# Schematic_Sensing_Module.net
KiCad netlist of a schematic drawn in EAGLE
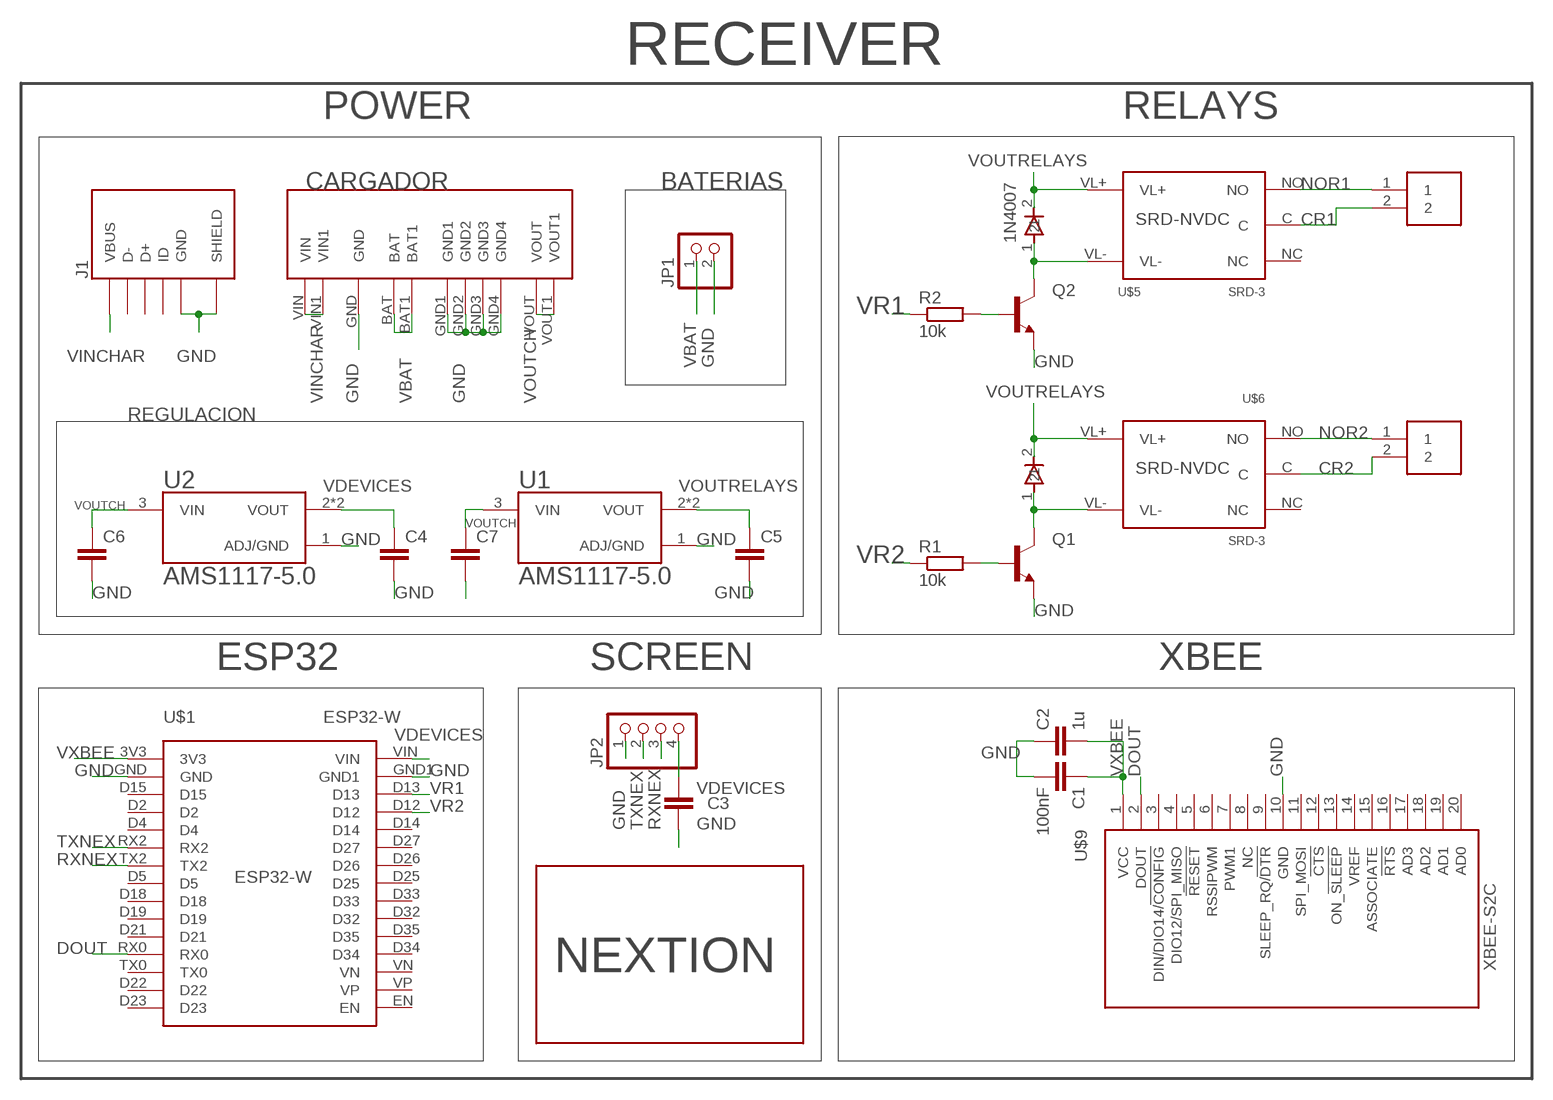
[diagram p0: schematic, sheet 1]

(export (version "E")
  (design (tool "Eeschema 10.0.6"))
  (components
    (comp (ref "1N4007")
      (value "1N4007SMA")
      (footprint "eagle-import:SMA")
      (libsource (lib "eagle-import") (part "1N4007SMA"))
    )
    (comp (ref "1N4007SMA")
      (value "1N4007SMA")
      (footprint "eagle-import:SMA")
      (libsource (lib "eagle-import") (part "1N4007SMA"))
    )
    (comp (ref "C1")
      (value "100nF")
      (footprint "eagle-import:C1206")
      (libsource (lib "eagle-import") (part "C-EUC1206"))
    )
    (comp (ref "C2")
      (value "1u")
      (footprint "eagle-import:C1206")
      (libsource (lib "eagle-import") (part "C-EUC1206"))
    )
    (comp (ref "C3")
      (value "100nF")
      (footprint "eagle-import:C1206")
      (libsource (lib "eagle-import") (part "C-EUC1206"))
    )
    (comp (ref "C4")
      (value "C-EUC1206")
      (footprint "eagle-import:C1206")
      (libsource (lib "eagle-import") (part "C-EUC1206"))
    )
    (comp (ref "C5")
      (value "C-EUC1206")
      (footprint "eagle-import:C1206")
      (libsource (lib "eagle-import") (part "C-EUC1206"))
    )
    (comp (ref "C6")
      (value "C-EUC1206")
      (footprint "eagle-import:C1206")
      (libsource (lib "eagle-import") (part "C-EUC1206"))
    )
    (comp (ref "C7")
      (value "C-EUC1206")
      (footprint "eagle-import:C1206")
      (libsource (lib "eagle-import") (part "C-EUC1206"))
    )
    (comp (ref "CARGADOR")
      (value "MODULO_CARGA_5V")
      (footprint "eagle-import:MODULO_CARGA_5V")
      (libsource (lib "eagle-import") (part "MODULO_CARGA_5V"))
    )
    (comp (ref "J1")
      (value "USB3090-XX-X_REVE")
      (footprint "eagle-import:GCT_USB3090-XX-X_REVE")
      (fields (field (name "MF") "Global Connector Technology") (field (name "MP") "USB3090-30-A"))
      (libsource (lib "eagle-import") (part "USB3090-XX-X_REVE"))
    )
    (comp (ref "JP1")
      (value "PINHD-1X2")
      (footprint "eagle-import:1X02")
      (libsource (lib "eagle-import") (part "PINHD-1X2"))
    )
    (comp (ref "JP2")
      (value "PINHD-1X4")
      (footprint "eagle-import:1X04")
      (libsource (lib "eagle-import") (part "PINHD-1X4"))
    )
    (comp (ref "Q1")
      (value "MMBT2222A")
      (footprint "eagle-import:SOT23")
      (fields (field (name "MF") "ON Semiconductor"))
      (libsource (lib "eagle-import") (part "MMBT2222A"))
    )
    (comp (ref "Q2")
      (value "MMBT2222A")
      (footprint "eagle-import:SOT23")
      (fields (field (name "MF") "ON Semiconductor"))
      (libsource (lib "eagle-import") (part "MMBT2222A"))
    )
    (comp (ref "R1")
      (value "10k")
      (footprint "eagle-import:R1206")
      (libsource (lib "eagle-import") (part "R-EU_R1206"))
    )
    (comp (ref "R2")
      (value "10k")
      (footprint "eagle-import:R1206")
      (libsource (lib "eagle-import") (part "R-EU_R1206"))
    )
    (comp (ref "REL1")
      (value "TERMINAL-TB2")
      (footprint "eagle-import:TERMINAL-TB2")
      (libsource (lib "eagle-import") (part "TERMINAL-TB2"))
    )
    (comp (ref "REL2")
      (value "TERMINAL-TB2")
      (footprint "eagle-import:TERMINAL-TB2")
      (libsource (lib "eagle-import") (part "TERMINAL-TB2"))
    )
    (comp (ref "U$1")
      (value "ESP32-W")
      (footprint "eagle-import:DIP")
      (libsource (lib "eagle-import") (part "ESP32-W"))
    )
    (comp (ref "U$2")
      (value "NX4024T032")
      (footprint "eagle-import:NX4024T032")
      (libsource (lib "eagle-import") (part "NX4024T032"))
    )
    (comp (ref "U$5")
      (value "SRD-3")
      (footprint "eagle-import:SRD-N")
      (libsource (lib "eagle-import") (part "SRD-3"))
    )
    (comp (ref "U$6")
      (value "SRD-3")
      (footprint "eagle-import:SRD-N")
      (libsource (lib "eagle-import") (part "SRD-3"))
    )
    (comp (ref "U$9")
      (value "XBEE-S2C")
      (footprint "eagle-import:XBEE-DIP")
      (libsource (lib "eagle-import") (part "XBEE-S2C"))
    )
    (comp (ref "U1")
      (value "AMS1117-5.0")
      (footprint "eagle-import:SOT229P700X180-4N")
      (fields (field (name "MF") "Advanced Monolithic Systems"))
      (libsource (lib "eagle-import") (part "AMS1117-5.0"))
    )
    (comp (ref "U2")
      (value "AMS1117-5.0")
      (footprint "eagle-import:SOT229P700X180-4N")
      (fields (field (name "MF") "Advanced Monolithic Systems"))
      (libsource (lib "eagle-import") (part "AMS1117-5.0"))
    )
  )
  (nets
    (net (code "1") (name "/CR1") (class "Default")
      (node (ref "REL1") (pin "2") (pinfunction "2_2") (pintype "bidirectional"))
      (node (ref "U$5") (pin "C") (pinfunction "C_C") (pintype "bidirectional"))
    )
    (net (code "2") (name "/CR2") (class "Default")
      (node (ref "REL2") (pin "2") (pinfunction "2_2") (pintype "bidirectional"))
      (node (ref "U$6") (pin "C") (pinfunction "C_C") (pintype "bidirectional"))
    )
    (net (code "3") (name "/DOUT") (class "Default")
      (node (ref "U$1") (pin "RX0") (pinfunction "RX0_RX0") (pintype "bidirectional"))
      (node (ref "U$9") (pin "2") (pinfunction "DOUT_2") (pintype "bidirectional"))
    )
    (net (code "4") (name "/GND") (class "Default")
      (node (ref "C1") (pin "2") (pinfunction "2_2") (pintype "passive"))
      (node (ref "C2") (pin "1") (pinfunction "1_1") (pintype "passive"))
      (node (ref "C3") (pin "2") (pinfunction "2_2") (pintype "passive"))
      (node (ref "C4") (pin "2") (pinfunction "2_2") (pintype "passive"))
      (node (ref "C5") (pin "2") (pinfunction "2_2") (pintype "passive"))
      (node (ref "C6") (pin "2") (pinfunction "2_2") (pintype "passive"))
      (node (ref "C7") (pin "2") (pinfunction "2_2") (pintype "passive"))
      (node (ref "CARGADOR") (pin "GND") (pinfunction "GND_GND") (pintype "bidirectional"))
      (node (ref "CARGADOR") (pin "GND1") (pinfunction "GND1_GND1") (pintype "bidirectional"))
      (node (ref "CARGADOR") (pin "GND2") (pinfunction "GND2_GND2") (pintype "bidirectional"))
      (node (ref "CARGADOR") (pin "GND3") (pinfunction "GND3_GND3") (pintype "bidirectional"))
      (node (ref "CARGADOR") (pin "GND4") (pinfunction "GND4_GND4") (pintype "bidirectional"))
      (node (ref "J1") (pin "5") (pinfunction "GND_5") (pintype "power_in"))
      (node (ref "J1") (pin "6") (pinfunction "SHIELD_6") (pintype "power_in"))
      (node (ref "J1") (pin "7") (pinfunction "SHIELD_7") (pintype "power_in"))
      (node (ref "J1") (pin "8") (pinfunction "SHIELD_8") (pintype "power_in"))
      (node (ref "J1") (pin "9") (pinfunction "SHIELD_9") (pintype "power_in"))
      (node (ref "JP1") (pin "2") (pinfunction "2_2") (pintype "passive"))
      (node (ref "JP2") (pin "1") (pinfunction "1_1") (pintype "passive"))
      (node (ref "Q1") (pin "2") (pinfunction "E_2") (pintype "passive"))
      (node (ref "Q2") (pin "2") (pinfunction "E_2") (pintype "passive"))
      (node (ref "U$1") (pin "GND") (pinfunction "GND_GND") (pintype "bidirectional"))
      (node (ref "U$1") (pin "GND1") (pinfunction "GND1_GND1") (pintype "bidirectional"))
      (node (ref "U$9") (pin "10") (pinfunction "GND_10") (pintype "bidirectional"))
      (node (ref "U1") (pin "1") (pinfunction "ADJ/GND_1") (pintype "power_in"))
      (node (ref "U2") (pin "1") (pinfunction "ADJ/GND_1") (pintype "power_in"))
    )
    (net (code "5") (name "/NOR1") (class "Default")
      (node (ref "REL1") (pin "1") (pinfunction "1_1") (pintype "bidirectional"))
      (node (ref "U$5") (pin "NO") (pinfunction "NO_NO") (pintype "bidirectional"))
    )
    (net (code "6") (name "/NOR2") (class "Default")
      (node (ref "REL2") (pin "1") (pinfunction "1_1") (pintype "bidirectional"))
      (node (ref "U$6") (pin "NO") (pinfunction "NO_NO") (pintype "bidirectional"))
    )
    (net (code "7") (name "/RXNEX") (class "Default")
      (node (ref "JP2") (pin "3") (pinfunction "3_3") (pintype "passive"))
      (node (ref "U$1") (pin "TX2") (pinfunction "TX2_TX2") (pintype "bidirectional"))
    )
    (net (code "8") (name "/TXNEX") (class "Default")
      (node (ref "JP2") (pin "2") (pinfunction "2_2") (pintype "passive"))
      (node (ref "U$1") (pin "RX2") (pinfunction "RX2_RX2") (pintype "bidirectional"))
    )
    (net (code "9") (name "/VBAT") (class "Default")
      (node (ref "CARGADOR") (pin "BAT") (pinfunction "BAT_BAT") (pintype "bidirectional"))
      (node (ref "CARGADOR") (pin "BAT1") (pinfunction "BAT1_BAT1") (pintype "bidirectional"))
      (node (ref "JP1") (pin "1") (pinfunction "1_1") (pintype "passive"))
    )
    (net (code "10") (name "/VDEVICES") (class "Default")
      (node (ref "C3") (pin "1") (pinfunction "1_1") (pintype "passive"))
      (node (ref "C4") (pin "1") (pinfunction "1_1") (pintype "passive"))
      (node (ref "JP2") (pin "4") (pinfunction "4_4") (pintype "passive"))
      (node (ref "U$1") (pin "VIN") (pinfunction "VIN_VIN") (pintype "bidirectional"))
      (node (ref "U2") (pin "2") (pinfunction "VOUT_2") (pintype "output"))
      (node (ref "U2") (pin "4") (pinfunction "VOUT_4") (pintype "output"))
    )
    (net (code "11") (name "/VINCHAR") (class "Default")
      (node (ref "CARGADOR") (pin "VIN") (pinfunction "VIN_VIN") (pintype "bidirectional"))
      (node (ref "CARGADOR") (pin "VIN1") (pinfunction "VIN1_VIN1") (pintype "bidirectional"))
      (node (ref "J1") (pin "1") (pinfunction "VBUS_1") (pintype "power_in"))
    )
    (net (code "12") (name "/VOUTCH") (class "Default")
      (node (ref "C6") (pin "1") (pinfunction "1_1") (pintype "passive"))
      (node (ref "C7") (pin "1") (pinfunction "1_1") (pintype "passive"))
      (node (ref "CARGADOR") (pin "VOUT") (pinfunction "VOUT_VOUT") (pintype "bidirectional"))
      (node (ref "CARGADOR") (pin "VOUT1") (pinfunction "VOUT1_VOUT1") (pintype "bidirectional"))
      (node (ref "U1") (pin "3") (pinfunction "VIN_3") (pintype "input"))
      (node (ref "U2") (pin "3") (pinfunction "VIN_3") (pintype "input"))
    )
    (net (code "13") (name "/VOUTRELAYS") (class "Default")
      (node (ref "1N4007") (pin "2") (pinfunction "2_2") (pintype "bidirectional"))
      (node (ref "1N4007SMA") (pin "2") (pinfunction "2_2") (pintype "bidirectional"))
      (node (ref "C5") (pin "1") (pinfunction "1_1") (pintype "passive"))
      (node (ref "U$5") (pin "VL+") (pinfunction "VL+_VL+") (pintype "bidirectional"))
      (node (ref "U$6") (pin "VL+") (pinfunction "VL+_VL+") (pintype "bidirectional"))
      (node (ref "U1") (pin "2") (pinfunction "VOUT_2") (pintype "output"))
      (node (ref "U1") (pin "4") (pinfunction "VOUT_4") (pintype "output"))
    )
    (net (code "14") (name "/VR1") (class "Default")
      (node (ref "R2") (pin "1") (pinfunction "1_1") (pintype "passive"))
      (node (ref "U$1") (pin "D13") (pinfunction "D13_D13") (pintype "bidirectional"))
    )
    (net (code "15") (name "/VR2") (class "Default")
      (node (ref "R1") (pin "1") (pinfunction "1_1") (pintype "passive"))
      (node (ref "U$1") (pin "D12") (pinfunction "D12_D12") (pintype "bidirectional"))
    )
    (net (code "16") (name "/VXBEE") (class "Default")
      (node (ref "C1") (pin "1") (pinfunction "1_1") (pintype "passive"))
      (node (ref "C2") (pin "2") (pinfunction "2_2") (pintype "passive"))
      (node (ref "U$1") (pin "3V3") (pinfunction "3V3_3V3") (pintype "bidirectional"))
      (node (ref "U$9") (pin "1") (pinfunction "VCC_1") (pintype "bidirectional"))
    )
    (net (code "17") (name "Net-(Q1-B)") (class "Default")
      (node (ref "Q1") (pin "1") (pinfunction "B_1") (pintype "passive"))
      (node (ref "R1") (pin "2") (pinfunction "2_2") (pintype "passive"))
    )
    (net (code "18") (name "Net-(Q1-C)") (class "Default")
      (node (ref "1N4007SMA") (pin "1") (pinfunction "1_1") (pintype "bidirectional"))
      (node (ref "Q1") (pin "3") (pinfunction "C_3") (pintype "passive"))
      (node (ref "U$6") (pin "VL-") (pinfunction "VL-_VL-") (pintype "bidirectional"))
    )
    (net (code "19") (name "Net-(Q2-B)") (class "Default")
      (node (ref "Q2") (pin "1") (pinfunction "B_1") (pintype "passive"))
      (node (ref "R2") (pin "2") (pinfunction "2_2") (pintype "passive"))
    )
    (net (code "20") (name "Net-(Q2-C)") (class "Default")
      (node (ref "1N4007") (pin "1") (pinfunction "1_1") (pintype "bidirectional"))
      (node (ref "Q2") (pin "3") (pinfunction "C_3") (pintype "passive"))
      (node (ref "U$5") (pin "VL-") (pinfunction "VL-_VL-") (pintype "bidirectional"))
    )
    (net (code "21") (name "unconnected-(J1-D+-Pad3)") (class "Default")
      (node (ref "J1") (pin "3") (pinfunction "D+_3") (pintype "bidirectional"))
    )
    (net (code "22") (name "unconnected-(J1-D--Pad2)") (class "Default")
      (node (ref "J1") (pin "2") (pinfunction "D-_2") (pintype "bidirectional"))
    )
    (net (code "23") (name "unconnected-(J1-ID-Pad4)") (class "Default")
      (node (ref "J1") (pin "4") (pinfunction "ID_4") (pintype "bidirectional"))
    )
    (net (code "24") (name "unconnected-(U$1-PadD2)") (class "Default")
      (node (ref "U$1") (pin "D2") (pinfunction "D2_D2") (pintype "bidirectional"))
    )
    (net (code "25") (name "unconnected-(U$1-PadD4)") (class "Default")
      (node (ref "U$1") (pin "D4") (pinfunction "D4_D4") (pintype "bidirectional"))
    )
    (net (code "26") (name "unconnected-(U$1-PadD5)") (class "Default")
      (node (ref "U$1") (pin "D5") (pinfunction "D5_D5") (pintype "bidirectional"))
    )
    (net (code "27") (name "unconnected-(U$1-PadD14)") (class "Default")
      (node (ref "U$1") (pin "D14") (pinfunction "D14_D14") (pintype "bidirectional"))
    )
    (net (code "28") (name "unconnected-(U$1-PadD15)") (class "Default")
      (node (ref "U$1") (pin "D15") (pinfunction "D15_D15") (pintype "bidirectional"))
    )
    (net (code "29") (name "unconnected-(U$1-PadD18)") (class "Default")
      (node (ref "U$1") (pin "D18") (pinfunction "D18_D18") (pintype "bidirectional"))
    )
    (net (code "30") (name "unconnected-(U$1-PadD19)") (class "Default")
      (node (ref "U$1") (pin "D19") (pinfunction "D19_D19") (pintype "bidirectional"))
    )
    (net (code "31") (name "unconnected-(U$1-PadD21)") (class "Default")
      (node (ref "U$1") (pin "D21") (pinfunction "D21_D21") (pintype "bidirectional"))
    )
    (net (code "32") (name "unconnected-(U$1-PadD22)") (class "Default")
      (node (ref "U$1") (pin "D22") (pinfunction "D22_D22") (pintype "bidirectional"))
    )
    (net (code "33") (name "unconnected-(U$1-PadD23)") (class "Default")
      (node (ref "U$1") (pin "D23") (pinfunction "D23_D23") (pintype "bidirectional"))
    )
    (net (code "34") (name "unconnected-(U$1-PadD25)") (class "Default")
      (node (ref "U$1") (pin "D25") (pinfunction "D25_D25") (pintype "bidirectional"))
    )
    (net (code "35") (name "unconnected-(U$1-PadD26)") (class "Default")
      (node (ref "U$1") (pin "D26") (pinfunction "D26_D26") (pintype "bidirectional"))
    )
    (net (code "36") (name "unconnected-(U$1-PadD27)") (class "Default")
      (node (ref "U$1") (pin "D27") (pinfunction "D27_D27") (pintype "bidirectional"))
    )
    (net (code "37") (name "unconnected-(U$1-PadD32)") (class "Default")
      (node (ref "U$1") (pin "D32") (pinfunction "D32_D32") (pintype "bidirectional"))
    )
    (net (code "38") (name "unconnected-(U$1-PadD33)") (class "Default")
      (node (ref "U$1") (pin "D33") (pinfunction "D33_D33") (pintype "bidirectional"))
    )
    (net (code "39") (name "unconnected-(U$1-PadD34)") (class "Default")
      (node (ref "U$1") (pin "D34") (pinfunction "D34_D34") (pintype "bidirectional"))
    )
    (net (code "40") (name "unconnected-(U$1-PadD35)") (class "Default")
      (node (ref "U$1") (pin "D35") (pinfunction "D35_D35") (pintype "bidirectional"))
    )
    (net (code "41") (name "unconnected-(U$1-PadEN)") (class "Default")
      (node (ref "U$1") (pin "EN") (pinfunction "EN_EN") (pintype "bidirectional"))
    )
    (net (code "42") (name "unconnected-(U$1-PadTX0)") (class "Default")
      (node (ref "U$1") (pin "TX0") (pinfunction "TX0_TX0") (pintype "bidirectional"))
    )
    (net (code "43") (name "unconnected-(U$1-PadVN)") (class "Default")
      (node (ref "U$1") (pin "VN") (pinfunction "VN_VN") (pintype "bidirectional"))
    )
    (net (code "44") (name "unconnected-(U$1-PadVP)") (class "Default")
      (node (ref "U$1") (pin "VP") (pinfunction "VP_VP") (pintype "bidirectional"))
    )
    (net (code "45") (name "unconnected-(U$5-PadNC)") (class "Default")
      (node (ref "U$5") (pin "NC") (pinfunction "NC_NC") (pintype "bidirectional"))
    )
    (net (code "46") (name "unconnected-(U$6-PadNC)") (class "Default")
      (node (ref "U$6") (pin "NC") (pinfunction "NC_NC") (pintype "bidirectional"))
    )
    (net (code "47") (name "unconnected-(U$9-AD0-Pad20)") (class "Default")
      (node (ref "U$9") (pin "20") (pinfunction "AD0_20") (pintype "bidirectional"))
    )
    (net (code "48") (name "unconnected-(U$9-AD1-Pad19)") (class "Default")
      (node (ref "U$9") (pin "19") (pinfunction "AD1_19") (pintype "bidirectional"))
    )
    (net (code "49") (name "unconnected-(U$9-AD2-Pad18)") (class "Default")
      (node (ref "U$9") (pin "18") (pinfunction "AD2_18") (pintype "bidirectional"))
    )
    (net (code "50") (name "unconnected-(U$9-AD3-Pad17)") (class "Default")
      (node (ref "U$9") (pin "17") (pinfunction "AD3_17") (pintype "bidirectional"))
    )
    (net (code "51") (name "unconnected-(U$9-ASSOCIATE-Pad15)") (class "Default")
      (node (ref "U$9") (pin "15") (pinfunction "ASSOCIATE_15") (pintype "bidirectional"))
    )
    (net (code "52") (name "unconnected-(U$9-DIN{slash}DIO14{slash}~{CONFIG}-Pad3)") (class "Default")
      (node (ref "U$9") (pin "3") (pinfunction "DIN/DIO14/~{CONFIG}_3") (pintype "bidirectional"))
    )
    (net (code "53") (name "unconnected-(U$9-DIO12{slash}SPI_MISO-Pad4)") (class "Default")
      (node (ref "U$9") (pin "4") (pinfunction "DIO12/SPI_MISO_4") (pintype "bidirectional"))
    )
    (net (code "54") (name "unconnected-(U$9-NC-Pad8)") (class "Default")
      (node (ref "U$9") (pin "8") (pinfunction "NC_8") (pintype "bidirectional"))
    )
    (net (code "55") (name "unconnected-(U$9-ON_~{SLEEP}-Pad13)") (class "Default")
      (node (ref "U$9") (pin "13") (pinfunction "ON_~{SLEEP}_13") (pintype "bidirectional"))
    )
    (net (code "56") (name "unconnected-(U$9-PWM1-Pad7)") (class "Default")
      (node (ref "U$9") (pin "7") (pinfunction "PWM1_7") (pintype "bidirectional"))
    )
    (net (code "57") (name "unconnected-(U$9-RSSIPWM-Pad6)") (class "Default")
      (node (ref "U$9") (pin "6") (pinfunction "RSSIPWM_6") (pintype "bidirectional"))
    )
    (net (code "58") (name "unconnected-(U$9-SLEEP_RQ{slash}~{DTR}-Pad9)") (class "Default")
      (node (ref "U$9") (pin "9") (pinfunction "SLEEP_RQ/~{DTR}_9") (pintype "bidirectional"))
    )
    (net (code "59") (name "unconnected-(U$9-SPI_MOSI-Pad11)") (class "Default")
      (node (ref "U$9") (pin "11") (pinfunction "SPI_MOSI_11") (pintype "bidirectional"))
    )
    (net (code "60") (name "unconnected-(U$9-VREF-Pad14)") (class "Default")
      (node (ref "U$9") (pin "14") (pinfunction "VREF_14") (pintype "bidirectional"))
    )
    (net (code "61") (name "unconnected-(U$9-~{CTS}-Pad12)") (class "Default")
      (node (ref "U$9") (pin "12") (pinfunction "~{CTS}_12") (pintype "bidirectional"))
    )
    (net (code "62") (name "unconnected-(U$9-~{RESET}-Pad5)") (class "Default")
      (node (ref "U$9") (pin "5") (pinfunction "~{RESET}_5") (pintype "bidirectional"))
    )
    (net (code "63") (name "unconnected-(U$9-~{RTS}-Pad16)") (class "Default")
      (node (ref "U$9") (pin "16") (pinfunction "~{RTS}_16") (pintype "bidirectional"))
    )
  )
)
